# Sensors.net
KiCad netlist of a schematic drawn in Altium Designer
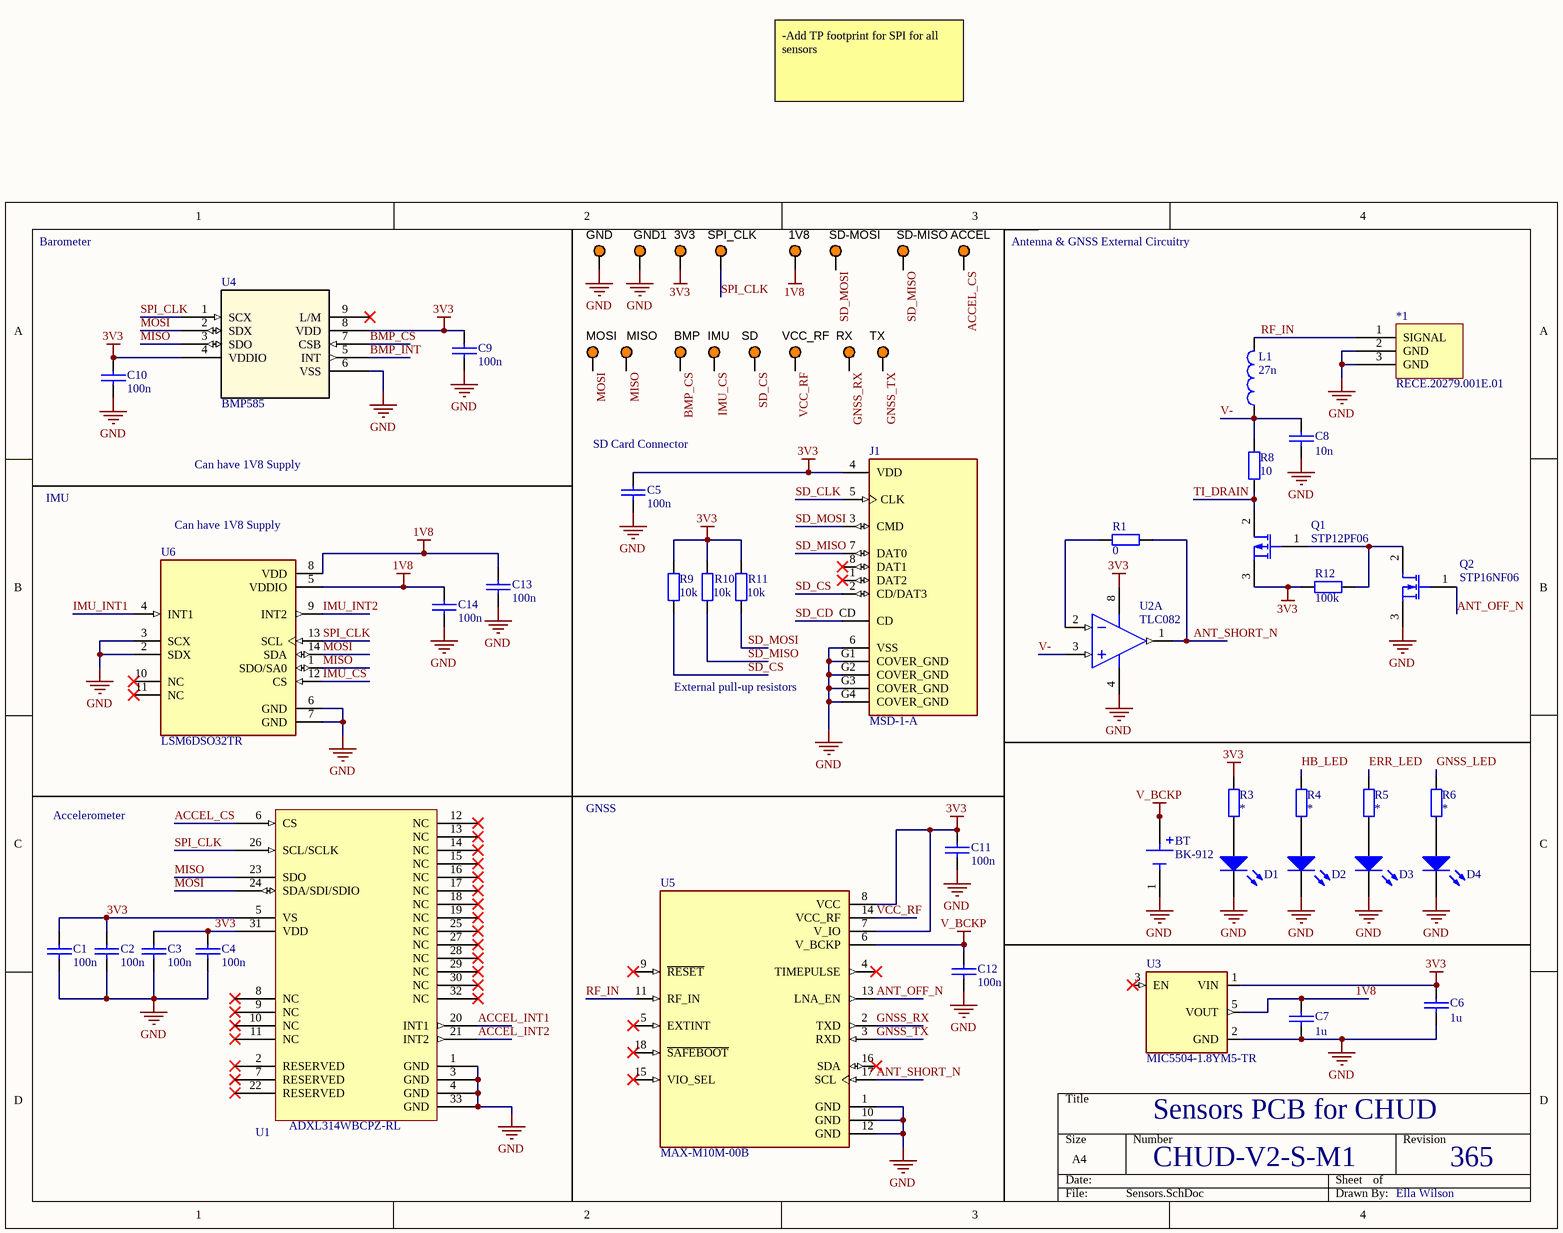
[diagram p0: Sensors.SchDoc]

(export (version "E")
  (design (tool "Eeschema 10.0.6"))
  (components
    (comp (ref "*1") (value "RECE.20279.001E.01") (libsource (lib "Schlib3") (part "RECE.20279.001E.01")))
    (comp (ref "1V8")
      (value "5003")
      (footprint "EE209_PcbLib:TP_TH")
      (description "Test Point, Orange, 1-Pin THD, RoHS")
      (libsource (lib "EE209_SchLib") (part "TestPoint"))
    )
    (comp (ref "3V3")
      (value "5003")
      (footprint "EE209_PcbLib:TP_TH")
      (description "Test Point, Orange, 1-Pin THD, RoHS")
      (libsource (lib "EE209_SchLib") (part "TestPoint"))
    )
    (comp (ref "ACCEL")
      (value "5003")
      (footprint "EE209_PcbLib:TP_TH")
      (description "Test Point, Orange, 1-Pin THD, RoHS")
      (libsource (lib "EE209_SchLib") (part "TestPoint"))
    )
    (comp (ref "BMP")
      (value "5003")
      (footprint "EE209_PcbLib:TP_TH")
      (description "Test Point, Orange, 1-Pin THD, RoHS")
      (libsource (lib "EE209_SchLib") (part "TestPoint"))
    )
    (comp (ref "BT")
      (value "BK-912")
      (footprint "BAT_BK-912")
      (description "BATTERY RETAINER COIN 20MM SMD")
      (fields (field (name "MF") "MPD"))
      (libsource (lib "BK-912") (part "BK-912"))
    )
    (comp (ref "C1")
      (value "100n")
      (footprint "0805 CAP")
      (description "SMT ceramic capacitor 0805 size")
      (libsource (lib "EE209_SchLib") (part "CerCap_SMT_0805"))
    )
    (comp (ref "C2")
      (value "100n")
      (footprint "0805 CAP")
      (description "SMT ceramic capacitor 0805 size")
      (libsource (lib "EE209_SchLib") (part "CerCap_SMT_0805"))
    )
    (comp (ref "C3")
      (value "100n")
      (footprint "0805 CAP")
      (description "SMT ceramic capacitor 0805 size")
      (libsource (lib "EE209_SchLib") (part "CerCap_SMT_0805"))
    )
    (comp (ref "C4")
      (value "100n")
      (footprint "0805 CAP")
      (description "SMT ceramic capacitor 0805 size")
      (libsource (lib "EE209_SchLib") (part "CerCap_SMT_0805"))
    )
    (comp (ref "C5")
      (value "100n")
      (footprint "0805 CAP")
      (description "SMT ceramic capacitor 0805 size")
      (libsource (lib "EE209_SchLib") (part "CerCap_SMT_0805"))
    )
    (comp (ref "C6")
      (value "1u")
      (footprint "0805 CAP")
      (description "SMT ceramic capacitor 0805 size")
      (libsource (lib "EE209_SchLib") (part "CerCap_SMT_0805"))
    )
    (comp (ref "C7")
      (value "1u")
      (footprint "0805 CAP")
      (description "SMT ceramic capacitor 0805 size")
      (libsource (lib "EE209_SchLib") (part "CerCap_SMT_0805"))
    )
    (comp (ref "C8")
      (value "10n")
      (footprint "0805 CAP")
      (description "SMT ceramic capacitor 0805 size")
      (libsource (lib "EE209_SchLib") (part "CerCap_SMT_0805"))
    )
    (comp (ref "C9")
      (value "100n")
      (footprint "0805 CAP")
      (description "SMT ceramic capacitor 0805 size")
      (libsource (lib "EE209_SchLib") (part "CerCap_SMT_0805"))
    )
    (comp (ref "C10")
      (value "100n")
      (footprint "0805 CAP")
      (description "SMT ceramic capacitor 0805 size")
      (libsource (lib "EE209_SchLib") (part "CerCap_SMT_0805"))
    )
    (comp (ref "C11")
      (value "100n")
      (footprint "0805 CAP")
      (description "SMT ceramic capacitor 0805 size")
      (libsource (lib "EE209_SchLib") (part "CerCap_SMT_0805"))
    )
    (comp (ref "C12")
      (value "100n")
      (footprint "0805 CAP")
      (description "SMT ceramic capacitor 0805 size")
      (libsource (lib "EE209_SchLib") (part "CerCap_SMT_0805"))
    )
    (comp (ref "C13")
      (value "100n")
      (footprint "0805 CAP")
      (description "SMT ceramic capacitor 0805 size")
      (libsource (lib "EE209_SchLib") (part "CerCap_SMT_0805"))
    )
    (comp (ref "C14")
      (value "100n")
      (footprint "0805 CAP")
      (description "SMT ceramic capacitor 0805 size")
      (libsource (lib "EE209_SchLib") (part "CerCap_SMT_0805"))
    )
    (comp (ref "D1")
      (value "LTST-C170KGKT")
      (footprint "0805 LED")
      (description "SMT LED 0805 size")
      (fields (field (name "MANUFACTURER") "Lite-On Inc."))
      (libsource (lib "EE209_SchLib") (part "LED_SMT_0805"))
    )
    (comp (ref "D2")
      (value "LTST-C170KGKT")
      (footprint "0805 LED")
      (description "SMT LED 0805 size")
      (fields (field (name "MANUFACTURER") "Lite-On Inc."))
      (libsource (lib "EE209_SchLib") (part "LED_SMT_0805"))
    )
    (comp (ref "D3")
      (value "LTST-C170KGKT")
      (footprint "0805 LED")
      (description "SMT LED 0805 size")
      (fields (field (name "MANUFACTURER") "Lite-On Inc."))
      (libsource (lib "EE209_SchLib") (part "LED_SMT_0805"))
    )
    (comp (ref "D4")
      (value "LTST-C170KGKT")
      (footprint "0805 LED")
      (description "SMT LED 0805 size")
      (fields (field (name "MANUFACTURER") "Lite-On Inc."))
      (libsource (lib "EE209_SchLib") (part "LED_SMT_0805"))
    )
    (comp (ref "GND")
      (value "5003")
      (footprint "EE209_PcbLib:TP_TH")
      (description "Test Point, Orange, 1-Pin THD, RoHS")
      (libsource (lib "EE209_SchLib") (part "TestPoint"))
    )
    (comp (ref "GND1")
      (value "5003")
      (footprint "EE209_PcbLib:TP_TH")
      (description "Test Point, Orange, 1-Pin THD, RoHS")
      (libsource (lib "EE209_SchLib") (part "TestPoint"))
    )
    (comp (ref "IMU")
      (value "5003")
      (footprint "EE209_PcbLib:TP_TH")
      (description "Test Point, Orange, 1-Pin THD, RoHS")
      (libsource (lib "EE209_SchLib") (part "TestPoint"))
    )
    (comp (ref "J1")
      (value "MSD-1-A")
      (footprint "CUI_MSD-1-A")
      (fields (field (name "MF") "Same Sky"))
      (libsource (lib "MSD-1-A") (part "MSD-1-A"))
    )
    (comp (ref "L1")
      (value "27n")
      (footprint "ece-INDUCTOR1005")
      (description "inductor Surface Mount")
      (libsource (lib "ece components") (part "Inductor"))
    )
    (comp (ref "MISO")
      (value "5003")
      (footprint "EE209_PcbLib:TP_TH")
      (description "Test Point, Orange, 1-Pin THD, RoHS")
      (libsource (lib "EE209_SchLib") (part "TestPoint"))
    )
    (comp (ref "MOSI")
      (value "5003")
      (footprint "EE209_PcbLib:TP_TH")
      (description "Test Point, Orange, 1-Pin THD, RoHS")
      (libsource (lib "EE209_SchLib") (part "TestPoint"))
    )
    (comp (ref "Q1")
      (value "STP12PF06")
      (footprint "ece-TO220")
      (description "P channel MOSFET")
      (libsource (lib "ece components") (part "STP12P"))
    )
    (comp (ref "Q2")
      (value "STP16NF06")
      (footprint "ece-TO220")
      (description "N channel MOSFET")
      (libsource (lib "ece components") (part "STP16N"))
    )
    (comp (ref "R1")
      (value "0")
      (footprint "0805 RES")
      (description "0805 resistor")
      (fields (field (name "PUBLISHER") "Altium Limited"))
      (libsource (lib "") (part "Res_SMT_0805_1"))
    )
    (comp (ref "R3")
      (value "*")
      (footprint "0805 RES")
      (description "0805 resistor")
      (fields (field (name "PUBLISHER") "Altium Limited"))
      (libsource (lib "EE209_SchLib") (part "Res_SMT_0805"))
    )
    (comp (ref "R4")
      (value "*")
      (footprint "0805 RES")
      (description "0805 resistor")
      (fields (field (name "PUBLISHER") "Altium Limited"))
      (libsource (lib "EE209_SchLib") (part "Res_SMT_0805"))
    )
    (comp (ref "R5")
      (value "*")
      (footprint "0805 RES")
      (description "0805 resistor")
      (fields (field (name "PUBLISHER") "Altium Limited"))
      (libsource (lib "EE209_SchLib") (part "Res_SMT_0805"))
    )
    (comp (ref "R6")
      (value "*")
      (footprint "0805 RES")
      (description "0805 resistor")
      (fields (field (name "PUBLISHER") "Altium Limited"))
      (libsource (lib "EE209_SchLib") (part "Res_SMT_0805"))
    )
    (comp (ref "R8")
      (value "10")
      (footprint "0805 RES")
      (description "0805 resistor")
      (fields (field (name "PUBLISHER") "Altium Limited"))
      (libsource (lib "EE209_SchLib") (part "Res_SMT_0805"))
    )
    (comp (ref "R9")
      (value "10k")
      (footprint "0805 RES")
      (description "0805 resistor")
      (fields (field (name "PUBLISHER") "Altium Limited"))
      (libsource (lib "") (part "Res_SMT_0805_2"))
    )
    (comp (ref "R10")
      (value "10k")
      (footprint "0805 RES")
      (description "0805 resistor")
      (fields (field (name "PUBLISHER") "Altium Limited"))
      (libsource (lib "EE209_SchLib") (part "Res_SMT_0805"))
    )
    (comp (ref "R11")
      (value "10k")
      (footprint "0805 RES")
      (description "0805 resistor")
      (fields (field (name "PUBLISHER") "Altium Limited"))
      (libsource (lib "EE209_SchLib") (part "Res_SMT_0805"))
    )
    (comp (ref "R12")
      (value "100k")
      (footprint "0805 RES")
      (description "0805 resistor")
      (fields (field (name "PUBLISHER") "Altium Limited"))
      (libsource (lib "") (part "Res_SMT_0805_1"))
    )
    (comp (ref "RX")
      (value "5003")
      (footprint "EE209_PcbLib:TP_TH")
      (description "Test Point, Orange, 1-Pin THD, RoHS")
      (libsource (lib "EE209_SchLib") (part "TestPoint"))
    )
    (comp (ref "SD")
      (value "5003")
      (footprint "EE209_PcbLib:TP_TH")
      (description "Test Point, Orange, 1-Pin THD, RoHS")
      (libsource (lib "EE209_SchLib") (part "TestPoint"))
    )
    (comp (ref "SD-MISO")
      (value "5003")
      (footprint "EE209_PcbLib:TP_TH")
      (description "Test Point, Orange, 1-Pin THD, RoHS")
      (libsource (lib "EE209_SchLib") (part "TestPoint"))
    )
    (comp (ref "SD-MOSI")
      (value "5003")
      (footprint "EE209_PcbLib:TP_TH")
      (description "Test Point, Orange, 1-Pin THD, RoHS")
      (libsource (lib "EE209_SchLib") (part "TestPoint"))
    )
    (comp (ref "SPI_CLK")
      (value "5003")
      (footprint "EE209_PcbLib:TP_TH")
      (description "Test Point, Orange, 1-Pin THD, RoHS")
      (libsource (lib "EE209_SchLib") (part "TestPoint"))
    )
    (comp (ref "TX")
      (value "5003")
      (footprint "EE209_PcbLib:TP_TH")
      (description "Test Point, Orange, 1-Pin THD, RoHS")
      (libsource (lib "EE209_SchLib") (part "TestPoint"))
    )
    (comp (ref "U1") (value "ADXL314WBCPZ-RL") (libsource (lib "Schlib3") (part "ADXL314WBCPZ-RL")))
    (comp (ref "U2")
      (value "TLC082")
      (footprint "SO - 8")
      (description "IC OPAMP GP 10MHZ 8SOIC")
      (fields
        (field (name "MANUFACTURER") "Texas Instruments")
        (field (name "MANUFACTURER PART NUMBER") "TLC082CDR")
      )
      (libsource (lib "EE209_SchLib") (part "TLC082_SMT_SOIC8"))
    )
    (comp (ref "U3")
      (value "MIC5504-1.8YM5-TR")
      (footprint "SOT23-5P95_280X145XL45X37N")
      (description "Linear Voltage Regulator IC Positive Fixed 1 Output 300mA SOT-23-5")
      (fields (field (name "MF") "Microchip"))
      (libsource (lib "MIC5504-1.8YM5-TR") (part "MIC5504-1.8YM5-TR"))
    )
    (comp (ref "U4")
      (value "BMP585")
      (footprint "LGA9_BMP585_BOS")
      (description "Description")
      (fields (field (name "COPYRIGHT") "Copyright (C) 2026 Ultra Librarian. All rights reserved."))
      (libsource (lib "BMP585") (part "BMP585"))
    )
    (comp (ref "U5")
      (value "MAX-M10M-00B")
      (footprint "XCVR_MAX-M10M-00B")
      (description "MAX-M10 RF Receiver BeiDou, Galileo, GLONASS, GNSS, GPS -164dBm Not Included")
      (fields (field (name "MF") "u-blox"))
      (libsource (lib "MAX-M10M-00B") (part "MAX-M10M-00B"))
    )
    (comp (ref "U6")
      (value "LSM6DSO32TR")
      (footprint "XDCR_LSM6DSO32TR")
      (description "Accelerometer, Gyroscope, Temperature, 6 Axis Sensor IÂ²C, SPI Output")
      (fields (field (name "MF") "STMicroelectronics"))
      (libsource (lib "LSM6DSO32TR") (part "LSM6DSO32TR"))
    )
    (comp (ref "VCC_RF")
      (value "5003")
      (footprint "EE209_PcbLib:TP_TH")
      (description "Test Point, Orange, 1-Pin THD, RoHS")
      (libsource (lib "EE209_SchLib") (part "TestPoint"))
    )
  )
  (nets
    (net (code "1") (name "/ACCEL_CS") (class "Default")
      (node (ref "ACCEL") (pin "1") (pinfunction "1_1") (pintype "passive"))
      (node (ref "U1") (pin "6") (pinfunction "CS_6") (pintype "input"))
    )
    (net (code "2") (name "/ACCEL_INT1") (class "Default")
      (node (ref "U1") (pin "20") (pinfunction "INT1_20") (pintype "output"))
    )
    (net (code "3") (name "/ACCEL_INT2") (class "Default")
      (node (ref "U1") (pin "21") (pinfunction "INT2_21") (pintype "output"))
    )
    (net (code "4") (name "/ANT_OFF_N") (class "Default")
      (node (ref "Q2") (pin "1") (pinfunction "G_1") (pintype "passive"))
      (node (ref "U5") (pin "13") (pinfunction "LNA_EN_13") (pintype "output"))
    )
    (net (code "5") (name "/ANT_SHORT_N") (class "Default")
      (node (ref "R1") (pin "1") (pinfunction "1_1") (pintype "passive"))
      (node (ref "U2") (pin "1") (pinfunction "VOUTA_1") (pintype "output"))
      (node (ref "U5") (pin "17") (pinfunction "SCL_17") (pintype "input"))
    )
    (net (code "6") (name "/BMP_CS") (class "Default")
      (node (ref "BMP") (pin "1") (pinfunction "1_1") (pintype "passive"))
      (node (ref "U4") (pin "7") (pinfunction "CSB_7") (pintype "input"))
    )
    (net (code "7") (name "/BMP_INT") (class "Default")
      (node (ref "U4") (pin "5") (pinfunction "INT_5") (pintype "output"))
    )
    (net (code "8") (name "/ERR_LED") (class "Default")
      (node (ref "R5") (pin "2") (pinfunction "2_2") (pintype "passive"))
    )
    (net (code "9") (name "/GNSS_LED") (class "Default")
      (node (ref "R6") (pin "2") (pinfunction "2_2") (pintype "passive"))
    )
    (net (code "10") (name "/GNSS_RX") (class "Default")
      (node (ref "RX") (pin "1") (pinfunction "1_1") (pintype "passive"))
      (node (ref "U5") (pin "2") (pinfunction "TXD_2") (pintype "output"))
    )
    (net (code "11") (name "/GNSS_TX") (class "Default")
      (node (ref "TX") (pin "1") (pinfunction "1_1") (pintype "passive"))
      (node (ref "U5") (pin "3") (pinfunction "RXD_3") (pintype "input"))
    )
    (net (code "12") (name "/HB_LED") (class "Default")
      (node (ref "R4") (pin "2") (pinfunction "2_2") (pintype "passive"))
    )
    (net (code "13") (name "/IMU_CS") (class "Default")
      (node (ref "IMU") (pin "1") (pinfunction "1_1") (pintype "passive"))
      (node (ref "U6") (pin "12") (pinfunction "CS_12") (pintype "input"))
    )
    (net (code "14") (name "/IMU_INT1") (class "Default")
      (node (ref "U6") (pin "4") (pinfunction "INT1_4") (pintype "input"))
    )
    (net (code "15") (name "/IMU_INT2") (class "Default")
      (node (ref "U6") (pin "9") (pinfunction "INT2_9") (pintype "output"))
    )
    (net (code "16") (name "/MISO") (class "Default")
      (node (ref "MISO") (pin "1") (pinfunction "1_1") (pintype "passive"))
      (node (ref "U1") (pin "23") (pinfunction "SDO_23") (pintype "passive"))
      (node (ref "U4") (pin "3") (pinfunction "SDO_3") (pintype "bidirectional"))
      (node (ref "U6") (pin "1") (pinfunction "SDO/SA0_1") (pintype "bidirectional"))
    )
    (net (code "17") (name "/MOSI") (class "Default")
      (node (ref "MOSI") (pin "1") (pinfunction "1_1") (pintype "passive"))
      (node (ref "U1") (pin "24") (pinfunction "SDA/SDI/SDIO_24") (pintype "bidirectional"))
      (node (ref "U4") (pin "2") (pinfunction "SDX_2") (pintype "bidirectional"))
      (node (ref "U6") (pin "14") (pinfunction "SDA_14") (pintype "bidirectional"))
    )
    (net (code "18") (name "/RF_IN") (class "Default")
      (node (ref "*1") (pin "1") (pinfunction "SIGNAL_1") (pintype "passive"))
      (node (ref "L1") (pin "2") (pinfunction "2_2") (pintype "passive"))
      (node (ref "U5") (pin "11") (pinfunction "RF_IN_11") (pintype "input"))
    )
    (net (code "19") (name "/SD_CD") (class "Default")
      (node (ref "J1") (pin "CD") (pinfunction "CD_CD") (pintype "passive"))
    )
    (net (code "20") (name "/SD_CLK") (class "Default")
      (node (ref "J1") (pin "5") (pinfunction "CLK_5") (pintype "input"))
    )
    (net (code "21") (name "/SD_CS") (class "Default")
      (node (ref "J1") (pin "2") (pinfunction "CD/DAT3_2") (pintype "bidirectional"))
      (node (ref "R9") (pin "2") (pinfunction "2_2") (pintype "passive"))
      (node (ref "SD") (pin "1") (pinfunction "1_1") (pintype "passive"))
    )
    (net (code "22") (name "/SD_MISO") (class "Default")
      (node (ref "J1") (pin "7") (pinfunction "DAT0_7") (pintype "bidirectional"))
      (node (ref "R10") (pin "1") (pinfunction "1_1") (pintype "passive"))
      (node (ref "SD-MISO") (pin "1") (pinfunction "1_1") (pintype "passive"))
    )
    (net (code "23") (name "/SD_MOSI") (class "Default")
      (node (ref "J1") (pin "3") (pinfunction "CMD_3") (pintype "bidirectional"))
      (node (ref "R11") (pin "1") (pinfunction "1_1") (pintype "passive"))
      (node (ref "SD-MOSI") (pin "1") (pinfunction "1_1") (pintype "passive"))
    )
    (net (code "24") (name "/SPI_CLK") (class "Default")
      (node (ref "SPI_CLK") (pin "1") (pinfunction "1_1") (pintype "passive"))
      (node (ref "U1") (pin "26") (pinfunction "SCL/SCLK_26") (pintype "input"))
      (node (ref "U4") (pin "1") (pinfunction "SCX_1") (pintype "input"))
      (node (ref "U6") (pin "13") (pinfunction "SCL_13") (pintype "input"))
    )
    (net (code "25") (name "/TI_DRAIN") (class "Default")
      (node (ref "Q1") (pin "2") (pinfunction "D_2") (pintype "passive"))
      (node (ref "R8") (pin "1") (pinfunction "1_1") (pintype "passive"))
    )
    (net (code "26") (name "/V-") (class "Default")
      (node (ref "C8") (pin "1") (pinfunction "1_1") (pintype "passive"))
      (node (ref "L1") (pin "1") (pinfunction "1_1") (pintype "passive"))
      (node (ref "R8") (pin "2") (pinfunction "2_2") (pintype "passive"))
      (node (ref "U2") (pin "3") (pinfunction "VINA+_3") (pintype "input"))
    )
    (net (code "27") (name "/VCC_RF") (class "Default")
      (node (ref "U5") (pin "14") (pinfunction "VCC_RF_14") (pintype "power_in"))
      (node (ref "VCC_RF") (pin "1") (pinfunction "1_1") (pintype "passive"))
    )
    (net (code "28") (name "1V8") (class "Default")
      (node (ref "1V8") (pin "1") (pinfunction "1_1") (pintype "passive"))
      (node (ref "C13") (pin "1") (pinfunction "1_1") (pintype "passive"))
      (node (ref "C14") (pin "1") (pinfunction "1_1") (pintype "passive"))
      (node (ref "C7") (pin "1") (pinfunction "1_1") (pintype "passive"))
      (node (ref "U3") (pin "5") (pinfunction "VOUT_5") (pintype "output"))
      (node (ref "U6") (pin "5") (pinfunction "VDDIO_5") (pintype "power_in"))
      (node (ref "U6") (pin "8") (pinfunction "VDD_8") (pintype "power_in"))
    )
    (net (code "29") (name "3V3") (class "Default")
      (node (ref "3V3") (pin "1") (pinfunction "1_1") (pintype "passive"))
      (node (ref "C1") (pin "1") (pinfunction "1_1") (pintype "passive"))
      (node (ref "C10") (pin "1") (pinfunction "1_1") (pintype "passive"))
      (node (ref "C11") (pin "1") (pinfunction "1_1") (pintype "passive"))
      (node (ref "C2") (pin "1") (pinfunction "1_1") (pintype "passive"))
      (node (ref "C3") (pin "1") (pinfunction "1_1") (pintype "passive"))
      (node (ref "C4") (pin "1") (pinfunction "1_1") (pintype "passive"))
      (node (ref "C5") (pin "1") (pinfunction "1_1") (pintype "passive"))
      (node (ref "C6") (pin "1") (pinfunction "1_1") (pintype "passive"))
      (node (ref "C9") (pin "1") (pinfunction "1_1") (pintype "passive"))
      (node (ref "J1") (pin "4") (pinfunction "VDD_4") (pintype "power_in"))
      (node (ref "Q1") (pin "3") (pinfunction "S_3") (pintype "passive"))
      (node (ref "R10") (pin "2") (pinfunction "2_2") (pintype "passive"))
      (node (ref "R11") (pin "2") (pinfunction "2_2") (pintype "passive"))
      (node (ref "R12") (pin "2") (pinfunction "2_2") (pintype "passive"))
      (node (ref "R3") (pin "2") (pinfunction "2_2") (pintype "passive"))
      (node (ref "R9") (pin "1") (pinfunction "1_1") (pintype "passive"))
      (node (ref "U1") (pin "31") (pinfunction "VDD_31") (pintype "passive"))
      (node (ref "U1") (pin "5") (pinfunction "VS_5") (pintype "passive"))
      (node (ref "U2") (pin "8") (pinfunction "VDD_8") (pintype "power_in"))
      (node (ref "U3") (pin "1") (pinfunction "VIN_1") (pintype "power_in"))
      (node (ref "U4") (pin "4") (pinfunction "VDDIO_4") (pintype "power_in"))
      (node (ref "U4") (pin "8") (pinfunction "VDD_8") (pintype "power_in"))
      (node (ref "U5") (pin "7") (pinfunction "V_IO_7") (pintype "power_in"))
      (node (ref "U5") (pin "8") (pinfunction "VCC_8") (pintype "power_in"))
    )
    (net (code "30") (name "GND") (class "Default")
      (node (ref "*1") (pin "2") (pinfunction "GND_2") (pintype "passive"))
      (node (ref "*1") (pin "3") (pinfunction "GND_3") (pintype "passive"))
      (node (ref "BT") (pin "1") (pinfunction "NEG_1") (pintype "passive"))
      (node (ref "C1") (pin "2") (pinfunction "2_2") (pintype "passive"))
      (node (ref "C10") (pin "2") (pinfunction "2_2") (pintype "passive"))
      (node (ref "C11") (pin "2") (pinfunction "2_2") (pintype "passive"))
      (node (ref "C12") (pin "2") (pinfunction "2_2") (pintype "passive"))
      (node (ref "C13") (pin "2") (pinfunction "2_2") (pintype "passive"))
      (node (ref "C14") (pin "2") (pinfunction "2_2") (pintype "passive"))
      (node (ref "C2") (pin "2") (pinfunction "2_2") (pintype "passive"))
      (node (ref "C3") (pin "2") (pinfunction "2_2") (pintype "passive"))
      (node (ref "C4") (pin "2") (pinfunction "2_2") (pintype "passive"))
      (node (ref "C5") (pin "2") (pinfunction "2_2") (pintype "passive"))
      (node (ref "C6") (pin "2") (pinfunction "2_2") (pintype "passive"))
      (node (ref "C7") (pin "2") (pinfunction "2_2") (pintype "passive"))
      (node (ref "C8") (pin "2") (pinfunction "2_2") (pintype "passive"))
      (node (ref "C9") (pin "2") (pinfunction "2_2") (pintype "passive"))
      (node (ref "D1") (pin "2") (pinfunction "K_2") (pintype "passive"))
      (node (ref "D2") (pin "2") (pinfunction "K_2") (pintype "passive"))
      (node (ref "D3") (pin "2") (pinfunction "K_2") (pintype "passive"))
      (node (ref "D4") (pin "2") (pinfunction "K_2") (pintype "passive"))
      (node (ref "GND") (pin "1") (pinfunction "1_1") (pintype "passive"))
      (node (ref "GND1") (pin "1") (pinfunction "1_1") (pintype "passive"))
      (node (ref "J1") (pin "6") (pinfunction "VSS_6") (pintype "power_in"))
      (node (ref "J1") (pin "G1") (pinfunction "COVER_GND_G1") (pintype "power_in"))
      (node (ref "J1") (pin "G2") (pinfunction "COVER_GND_G2") (pintype "power_in"))
      (node (ref "J1") (pin "G3") (pinfunction "COVER_GND_G3") (pintype "power_in"))
      (node (ref "J1") (pin "G4") (pinfunction "COVER_GND_G4") (pintype "power_in"))
      (node (ref "Q2") (pin "3") (pinfunction "S_3") (pintype "passive"))
      (node (ref "U1") (pin "1") (pinfunction "GND_1") (pintype "passive"))
      (node (ref "U1") (pin "3") (pinfunction "GND_3") (pintype "passive"))
      (node (ref "U1") (pin "33") (pinfunction "GND_33") (pintype "passive"))
      (node (ref "U1") (pin "4") (pinfunction "GND_4") (pintype "passive"))
      (node (ref "U2") (pin "4") (pinfunction "VSS_4") (pintype "power_in"))
      (node (ref "U3") (pin "2") (pinfunction "GND_2") (pintype "power_in"))
      (node (ref "U4") (pin "6") (pinfunction "VSS_6") (pintype "power_in"))
      (node (ref "U5") (pin "1") (pinfunction "GND_1") (pintype "power_in"))
      (node (ref "U5") (pin "10") (pinfunction "GND_10") (pintype "power_in"))
      (node (ref "U5") (pin "12") (pinfunction "GND_12") (pintype "power_in"))
      (node (ref "U6") (pin "2") (pinfunction "SDX_2") (pintype "passive"))
      (node (ref "U6") (pin "3") (pinfunction "SCX_3") (pintype "passive"))
      (node (ref "U6") (pin "6") (pinfunction "GND_6") (pintype "power_in"))
      (node (ref "U6") (pin "7") (pinfunction "GND_7") (pintype "power_in"))
    )
    (net (code "31") (name "Net-(D1-A)") (class "Default")
      (node (ref "D1") (pin "1") (pinfunction "A_1") (pintype "passive"))
      (node (ref "R3") (pin "1") (pinfunction "1_1") (pintype "passive"))
    )
    (net (code "32") (name "Net-(D2-A)") (class "Default")
      (node (ref "D2") (pin "1") (pinfunction "A_1") (pintype "passive"))
      (node (ref "R4") (pin "1") (pinfunction "1_1") (pintype "passive"))
    )
    (net (code "33") (name "Net-(D3-A)") (class "Default")
      (node (ref "D3") (pin "1") (pinfunction "A_1") (pintype "passive"))
      (node (ref "R5") (pin "1") (pinfunction "1_1") (pintype "passive"))
    )
    (net (code "34") (name "Net-(D4-A)") (class "Default")
      (node (ref "D4") (pin "1") (pinfunction "A_1") (pintype "passive"))
      (node (ref "R6") (pin "1") (pinfunction "1_1") (pintype "passive"))
    )
    (net (code "35") (name "Net-(Q1-G)") (class "Default")
      (node (ref "Q1") (pin "1") (pinfunction "G_1") (pintype "passive"))
      (node (ref "Q2") (pin "2") (pinfunction "D_2") (pintype "passive"))
      (node (ref "R12") (pin "1") (pinfunction "1_1") (pintype "passive"))
    )
    (net (code "36") (name "Net-(U2A-VINA-)") (class "Default")
      (node (ref "R1") (pin "2") (pinfunction "2_2") (pintype "passive"))
      (node (ref "U2") (pin "2") (pinfunction "VINA-_2") (pintype "input"))
    )
    (net (code "37") (name "V_BCKP") (class "Default")
      (node (ref "BT") (pin "S1") (pinfunction "POS_S1") (pintype "passive"))
      (node (ref "BT") (pin "S2") (pinfunction "POS_S2") (pintype "passive"))
      (node (ref "C12") (pin "1") (pinfunction "1_1") (pintype "passive"))
      (node (ref "U5") (pin "6") (pinfunction "V_BCKP_6") (pintype "power_in"))
    )
    (net (code "38") (name "unconnected-(J1-DAT1-Pad8)") (class "Default")
      (node (ref "J1") (pin "8") (pinfunction "DAT1_8") (pintype "bidirectional+no_connect"))
    )
    (net (code "39") (name "unconnected-(J1-DAT2-Pad1)") (class "Default")
      (node (ref "J1") (pin "1") (pinfunction "DAT2_1") (pintype "bidirectional+no_connect"))
    )
    (net (code "40") (name "unconnected-(U1-NC-Pad8)") (class "Default")
      (node (ref "U1") (pin "8") (pinfunction "NC_8") (pintype "passive+no_connect"))
    )
    (net (code "41") (name "unconnected-(U1-NC-Pad9)") (class "Default")
      (node (ref "U1") (pin "9") (pinfunction "NC_9") (pintype "passive+no_connect"))
    )
    (net (code "42") (name "unconnected-(U1-NC-Pad10)") (class "Default")
      (node (ref "U1") (pin "10") (pinfunction "NC_10") (pintype "passive+no_connect"))
    )
    (net (code "43") (name "unconnected-(U1-NC-Pad11)") (class "Default")
      (node (ref "U1") (pin "11") (pinfunction "NC_11") (pintype "passive+no_connect"))
    )
    (net (code "44") (name "unconnected-(U1-NC-Pad12)") (class "Default")
      (node (ref "U1") (pin "12") (pinfunction "NC_12") (pintype "passive+no_connect"))
    )
    (net (code "45") (name "unconnected-(U1-NC-Pad13)") (class "Default")
      (node (ref "U1") (pin "13") (pinfunction "NC_13") (pintype "passive+no_connect"))
    )
    (net (code "46") (name "unconnected-(U1-NC-Pad14)") (class "Default")
      (node (ref "U1") (pin "14") (pinfunction "NC_14") (pintype "passive+no_connect"))
    )
    (net (code "47") (name "unconnected-(U1-NC-Pad15)") (class "Default")
      (node (ref "U1") (pin "15") (pinfunction "NC_15") (pintype "passive+no_connect"))
    )
    (net (code "48") (name "unconnected-(U1-NC-Pad16)") (class "Default")
      (node (ref "U1") (pin "16") (pinfunction "NC_16") (pintype "passive+no_connect"))
    )
    (net (code "49") (name "unconnected-(U1-NC-Pad17)") (class "Default")
      (node (ref "U1") (pin "17") (pinfunction "NC_17") (pintype "passive+no_connect"))
    )
    (net (code "50") (name "unconnected-(U1-NC-Pad18)") (class "Default")
      (node (ref "U1") (pin "18") (pinfunction "NC_18") (pintype "passive+no_connect"))
    )
    (net (code "51") (name "unconnected-(U1-NC-Pad19)") (class "Default")
      (node (ref "U1") (pin "19") (pinfunction "NC_19") (pintype "passive+no_connect"))
    )
    (net (code "52") (name "unconnected-(U1-NC-Pad25)") (class "Default")
      (node (ref "U1") (pin "25") (pinfunction "NC_25") (pintype "passive+no_connect"))
    )
    (net (code "53") (name "unconnected-(U1-NC-Pad27)") (class "Default")
      (node (ref "U1") (pin "27") (pinfunction "NC_27") (pintype "passive+no_connect"))
    )
    (net (code "54") (name "unconnected-(U1-NC-Pad28)") (class "Default")
      (node (ref "U1") (pin "28") (pinfunction "NC_28") (pintype "passive+no_connect"))
    )
    (net (code "55") (name "unconnected-(U1-NC-Pad29)") (class "Default")
      (node (ref "U1") (pin "29") (pinfunction "NC_29") (pintype "passive+no_connect"))
    )
    (net (code "56") (name "unconnected-(U1-NC-Pad30)") (class "Default")
      (node (ref "U1") (pin "30") (pinfunction "NC_30") (pintype "passive+no_connect"))
    )
    (net (code "57") (name "unconnected-(U1-NC-Pad32)") (class "Default")
      (node (ref "U1") (pin "32") (pinfunction "NC_32") (pintype "passive+no_connect"))
    )
    (net (code "58") (name "unconnected-(U1-RESERVED-Pad2)") (class "Default")
      (node (ref "U1") (pin "2") (pinfunction "RESERVED_2") (pintype "passive+no_connect"))
    )
    (net (code "59") (name "unconnected-(U1-RESERVED-Pad7)") (class "Default")
      (node (ref "U1") (pin "7") (pinfunction "RESERVED_7") (pintype "passive+no_connect"))
    )
    (net (code "60") (name "unconnected-(U1-RESERVED-Pad22)") (class "Default")
      (node (ref "U1") (pin "22") (pinfunction "RESERVED_22") (pintype "passive+no_connect"))
    )
    (net (code "61") (name "unconnected-(U3-EN-Pad3)") (class "Default")
      (node (ref "U3") (pin "3") (pinfunction "EN_3") (pintype "input+no_connect"))
    )
    (net (code "62") (name "unconnected-(U4-L{slash}M-Pad9)") (class "Default")
      (node (ref "U4") (pin "9") (pinfunction "L/M_9") (pintype "passive+no_connect"))
    )
    (net (code "63") (name "unconnected-(U5-EXTINT-Pad5)") (class "Default")
      (node (ref "U5") (pin "5") (pinfunction "EXTINT_5") (pintype "input+no_connect"))
    )
    (net (code "64") (name "unconnected-(U5-SDA-Pad16)") (class "Default")
      (node (ref "U5") (pin "16") (pinfunction "SDA_16") (pintype "bidirectional+no_connect"))
    )
    (net (code "65") (name "unconnected-(U5-TIMEPULSE-Pad4)") (class "Default")
      (node (ref "U5") (pin "4") (pinfunction "TIMEPULSE_4") (pintype "output+no_connect"))
    )
    (net (code "66") (name "unconnected-(U5-VIO_SEL-Pad15)") (class "Default")
      (node (ref "U5") (pin "15") (pinfunction "VIO_SEL_15") (pintype "input+no_connect"))
    )
    (net (code "67") (name "unconnected-(U5-~{RESET}-Pad9)") (class "Default")
      (node (ref "U5") (pin "9") (pinfunction "~{RESET}_9") (pintype "input+no_connect"))
    )
    (net (code "68") (name "unconnected-(U5-~{SAFEBOOT}-Pad18)") (class "Default")
      (node (ref "U5") (pin "18") (pinfunction "~{SAFEBOOT}_18") (pintype "input+no_connect"))
    )
    (net (code "69") (name "unconnected-(U6-NC-Pad10)") (class "Default")
      (node (ref "U6") (pin "10") (pinfunction "NC_10") (pintype "passive+no_connect"))
    )
    (net (code "70") (name "unconnected-(U6-NC-Pad11)") (class "Default")
      (node (ref "U6") (pin "11") (pinfunction "NC_11") (pintype "passive+no_connect"))
    )
  )
)
